# Controller_SolarCharge.net
KiCad netlist of a schematic drawn in Altium Designer
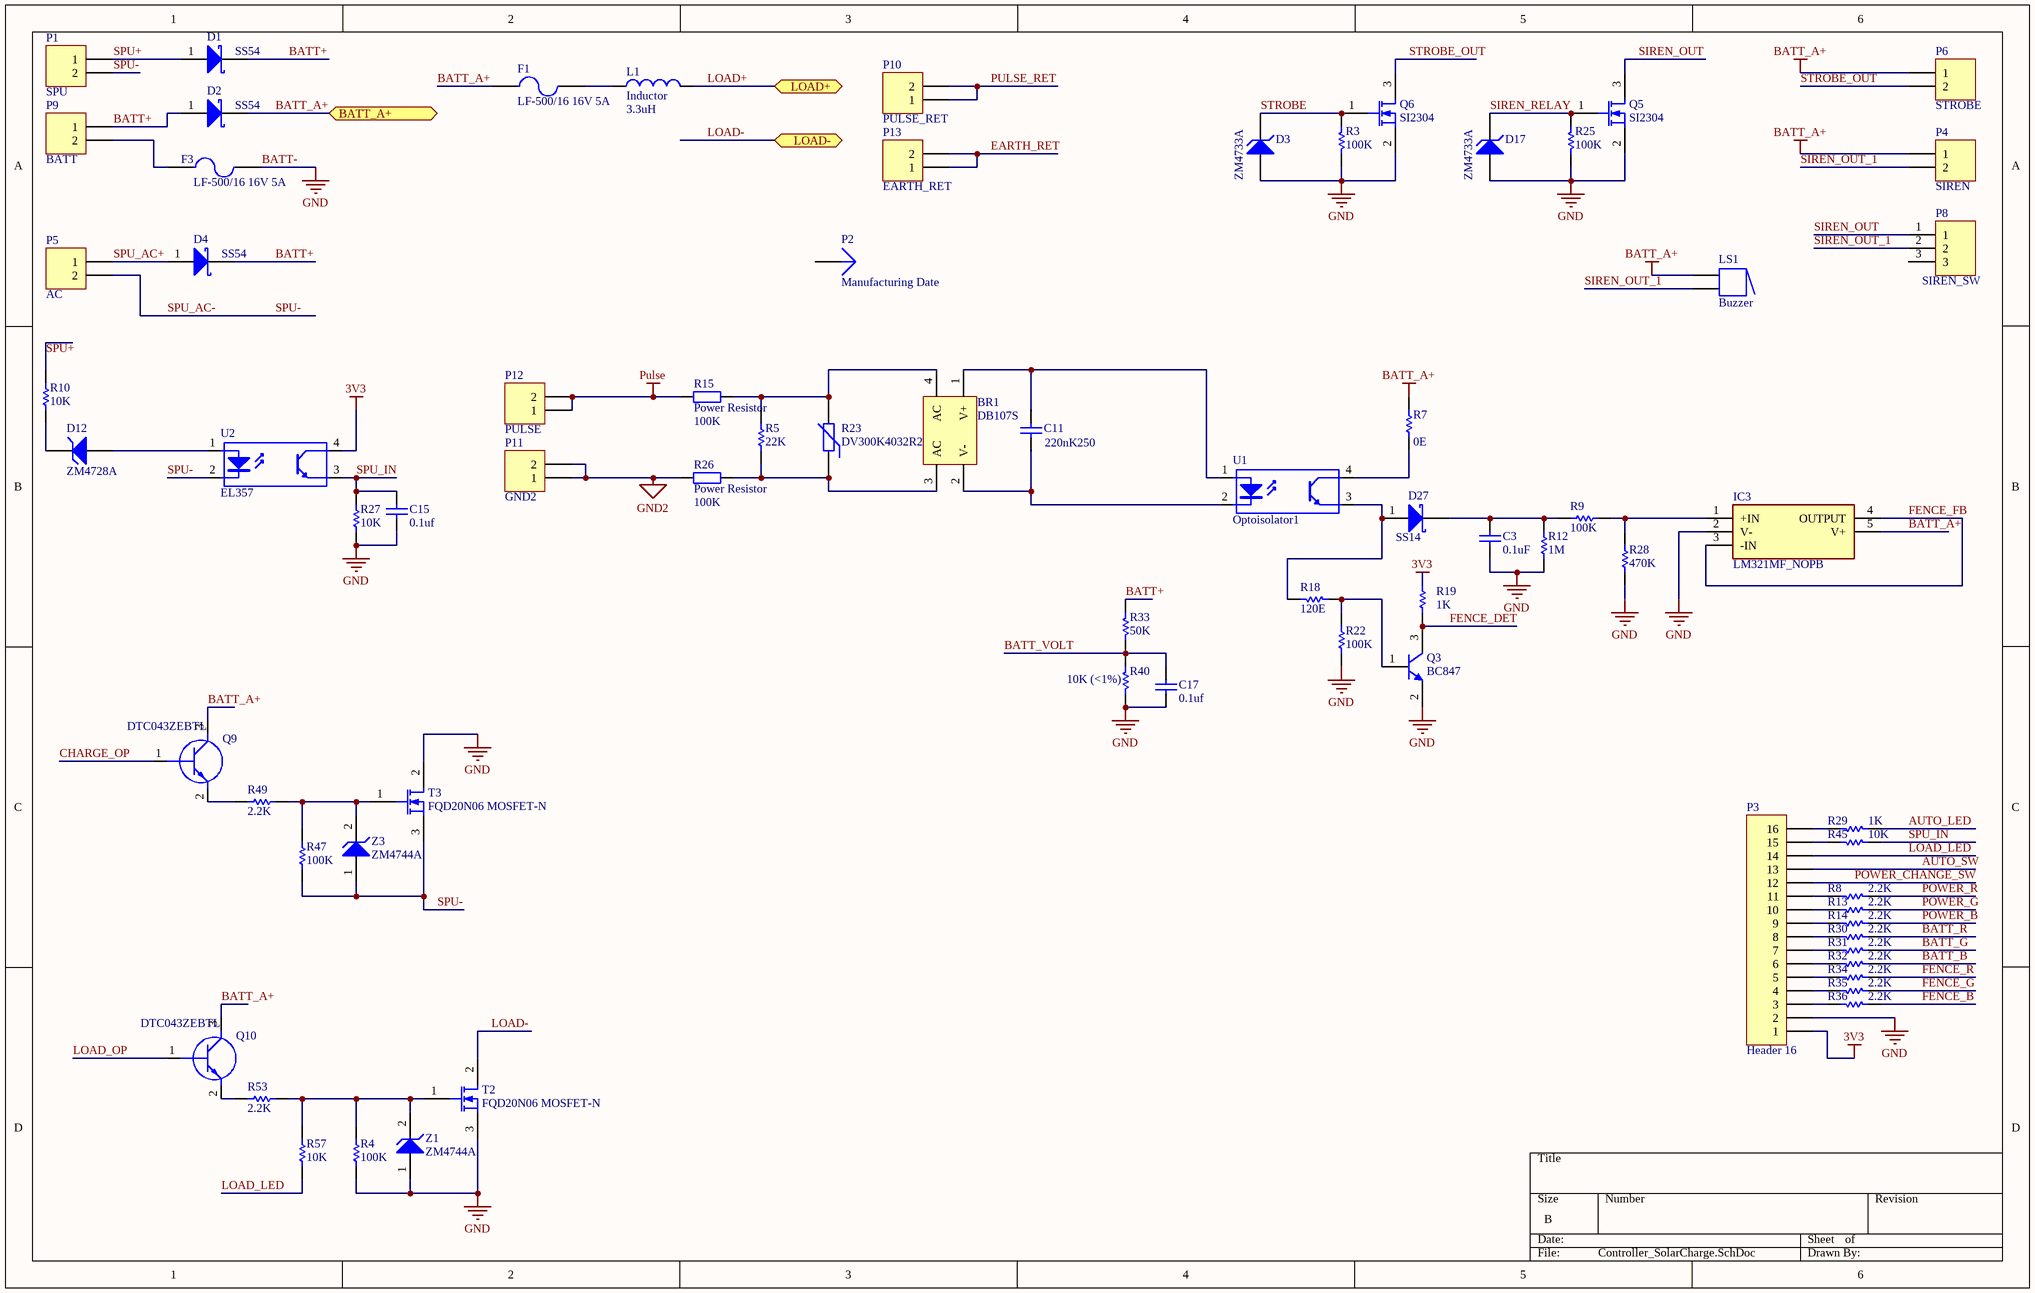
[diagram p0: Controller_SolarCharge.SchDoc]

(export (version "E")
  (design (tool "Eeschema 10.0.6"))
  (components
    (comp (ref "BR1")
      (value "DB107S")
      (footprint "DB-S_Bridge Rectifier")
      (description "Diode Bridge")
      (fields (field (name "PUBLISHER") "Altium Limited"))
      (libsource (lib "Miscellaneous Devices") (part "Bridge2"))
    )
    (comp (ref "C3")
      (value "0.1uF")
      (footprint "0805")
      (description "Capacitor")
      (fields (field (name "Comment") "Cap") (field (name "PUBLISHER") "Altium Limited"))
      (libsource (lib "Miscellaneous Devices") (part "Cap"))
    )
    (comp (ref "C11")
      (value "220nK250")
      (footprint "RES AXIAL-0.6")
      (description "Capacitor")
      (fields (field (name "Comment") "Cap") (field (name "PUBLISHER") "Altium Limited"))
      (libsource (lib "Miscellaneous Devices") (part "Cap"))
    )
    (comp (ref "C15")
      (value "0.1uf")
      (footprint "0805")
      (description "Capacitor")
      (fields (field (name "Comment") "Cap") (field (name "PUBLISHER") "Altium Limited"))
      (libsource (lib "Miscellaneous Devices") (part "Cap"))
    )
    (comp (ref "C17")
      (value "0.1uf")
      (footprint "0805")
      (description "Capacitor")
      (fields (field (name "Comment") "Cap") (field (name "PUBLISHER") "Altium Limited"))
      (libsource (lib "Miscellaneous Devices") (part "Cap"))
    )
    (comp (ref "D1")
      (value "SS54")
      (footprint "SMC")
      (description "Silicon RF Schottky Diode for Mixer Applications in the VHF/UHF Range")
      (fields (field (name "PUBLISHER") "Altium Limited"))
      (libsource (lib "Miscellaneous Devices") (part "Diode BAT17"))
    )
    (comp (ref "D2")
      (value "SS54")
      (footprint "SMDlibrary:SMC")
      (description "Silicon RF Schottky Diode for Mixer Applications in the VHF/UHF Range")
      (fields (field (name "PUBLISHER") "Altium Limited"))
      (libsource (lib "Miscellaneous Devices") (part "Diode BAT17"))
    )
    (comp (ref "D3")
      (value "ZM4733A")
      (footprint "SMA")
      (description "TVS Diode")
      (fields (field (name "PUBLISHER") "Altium Limited"))
      (libsource (lib "Miscellaneous Devices") (part "D Zener"))
    )
    (comp (ref "D4")
      (value "SS54")
      (footprint "SMDlibrary:SMC")
      (description "Silicon RF Schottky Diode for Mixer Applications in the VHF/UHF Range")
      (fields (field (name "PUBLISHER") "Altium Limited"))
      (libsource (lib "Miscellaneous Devices") (part "Diode BAT17"))
    )
    (comp (ref "D12")
      (value "ZM4728A")
      (footprint "SMDlibrary:SMA")
      (description "Zener Diode")
      (fields (field (name "PUBLISHER") "Altium Limited"))
      (libsource (lib "Miscellaneous Devices") (part "D Zener"))
    )
    (comp (ref "D17")
      (value "ZM4733A")
      (footprint "SMA")
      (description "TVS Diode")
      (fields (field (name "PUBLISHER") "Altium Limited"))
      (libsource (lib "Miscellaneous Devices") (part "D Zener"))
    )
    (comp (ref "D27")
      (value "SS14")
      (footprint "SMA")
      (description "Silicon RF Schottky Diode for Mixer Applications in the VHF/UHF Range")
      (fields (field (name "PUBLISHER") "Altium Limited"))
      (libsource (lib "Miscellaneous Devices") (part "Diode BAT17"))
    )
    (comp (ref "F1")
      (value "LF-500/16 16V 5A")
      (footprint "LF500-16")
      (description "Fuse")
      (fields (field (name "PUBLISHER") "Altium Limited"))
      (libsource (lib "Miscellaneous Devices") (part "Fuse 2"))
    )
    (comp (ref "F3")
      (value "LF-500/16 16V 5A")
      (footprint "LF500-16")
      (description "Fuse")
      (fields (field (name "PUBLISHER") "Altium Limited"))
      (libsource (lib "Miscellaneous Devices") (part "Fuse 2"))
    )
    (comp (ref "IC3")
      (value "LM321MF_NOPB")
      (footprint "SamacSys:SOT95P280X145-5N")
      (description "Integrated Circuit")
      (fields
        (field (name "MANUFACTURER_PART_NUMBER") "LM321MF/NOPB")
        (field (name "MOUSER PART NUMBER") "926-LM321MF/NOPB")
      )
      (libsource (lib "*") (part "LM321MF_NOPB"))
    )
    (comp (ref "L1")
      (value "Inductor")
      (footprint "Inductor_SMD_3.3uh")
      (fields (field (name "ALTIUM_VALUE") "3.3uH") (field (name "PUBLISHER") "Altium Limited"))
      (libsource (lib "Miscellaneous Devices") (part "Inductor"))
    )
    (comp (ref "LS1")
      (value "Buzzer")
      (footprint "BUZZER")
      (description "Magnetic Transducer Buzzer")
      (fields (field (name "PUBLISHER") "Altium Limited"))
      (libsource (lib "SchLib") (part "Buzzer"))
    )
    (comp (ref "P1")
      (value "SPU")
      (footprint "SCREW_TERMINAL 2PIN 5.08MM")
      (description "SCREW_TERMINAL 2PIN 5.08MM")
      (fields (field (name "PUBLISHER") "Altium Limited"))
      (libsource (lib "") (part "Header 2_1"))
    )
    (comp (ref "P2")
      (value "Manufacturing Date")
      (footprint "MFT_DATE")
      (description "Plug")
      (fields (field (name "PUBLISHER") "Altium Limited"))
      (libsource (lib "Miscellaneous Connectors") (part "Plug"))
    )
    (comp (ref "P3")
      (value "Header 16")
      (footprint "FPC_CON_16PIN")
      (description "Header, 16-Pin")
      (fields (field (name "PUBLISHER") "Altium Limited"))
      (libsource (lib "Miscellaneous Connectors") (part "Header 16"))
    )
    (comp (ref "P4")
      (value "SIREN")
      (footprint "SCREW_TERMINAL 2PIN 5.08MM")
      (description "SCREW_TERMINAL 2PIN 5.08MM")
      (fields (field (name "PUBLISHER") "Altium Limited"))
      (libsource (lib "Miscellaneous Connectors") (part "Header 2"))
    )
    (comp (ref "P5")
      (value "AC")
      (footprint "SCREW_TERMINAL 2PIN 5.08MM")
      (description "SCREW_TERMINAL 2PIN 5.08MM")
      (fields (field (name "PUBLISHER") "Altium Limited"))
      (libsource (lib "") (part "Header 2_1"))
    )
    (comp (ref "P6")
      (value "STROBE")
      (footprint "SCREW_TERMINAL 2PIN 5.08MM")
      (description "SCREW_TERMINAL 2PIN 5.08MM")
      (fields (field (name "PUBLISHER") "Altium Limited"))
      (libsource (lib "Miscellaneous Connectors") (part "Header 2"))
    )
    (comp (ref "P8")
      (value "SIREN_SW")
      (footprint "SWITCH_SLIDE")
      (description "Header, 3-Pin")
      (fields (field (name "PUBLISHER") "Altium Limited"))
      (libsource (lib "Miscellaneous Connectors") (part "Header 3"))
    )
    (comp (ref "P9")
      (value "BATT")
      (footprint "SCREW_TERMINAL 2PIN 5.08MM")
      (description "SCREW_TERMINAL 2PIN 5.08MM")
      (fields (field (name "PUBLISHER") "Altium Limited"))
      (libsource (lib "") (part "Header 2_1"))
    )
    (comp (ref "P10")
      (value "PULSE_RET")
      (footprint "SCREW_TERMINAL ENERGIZER")
      (description "SCREW_TERMINAL 2PIN 9.25MM")
      (fields (field (name "PUBLISHER") "Altium Limited"))
      (libsource (lib "") (part "Header 2_2"))
    )
    (comp (ref "P11")
      (value "GND2")
      (footprint "SCREW_TERMINAL ENERGIZER")
      (description "Header, 2-Pin")
      (fields (field (name "PUBLISHER") "Altium Limited"))
      (libsource (lib "") (part "Header 2_2"))
    )
    (comp (ref "P12")
      (value "PULSE")
      (footprint "SCREW_TERMINAL ENERGIZER")
      (description "SCREW_TERMINAL 2PIN 9.25MM")
      (fields (field (name "PUBLISHER") "Altium Limited"))
      (libsource (lib "") (part "Header 2_2"))
    )
    (comp (ref "P13")
      (value "EARTH_RET")
      (footprint "SCREW_TERMINAL ENERGIZER")
      (description "Header, 2-Pin")
      (fields (field (name "PUBLISHER") "Altium Limited"))
      (libsource (lib "") (part "Header 2_2"))
    )
    (comp (ref "Q3")
      (value "BC847")
      (footprint "SOT-23")
      (description "NPN General Purpose Amplifier")
      (fields (field (name "PUBLISHER") "Altium Limited"))
      (libsource (lib "Miscellaneous Devices") (part "2N3904"))
    )
    (comp (ref "Q5")
      (value "SI2304")
      (footprint "SOT-23")
      (description "SI2304 A4SHB MOSFET-N")
      (fields (field (name "PUBLISHER") "Altium Limited"))
      (libsource (lib "Miscellaneous Devices") (part "MOSFET-N"))
    )
    (comp (ref "Q6")
      (value "SI2304")
      (footprint "SOT-23")
      (description "SI2304 A4SHB MOSFET-N")
      (fields (field (name "PUBLISHER") "Altium Limited"))
      (libsource (lib "Miscellaneous Devices") (part "MOSFET-N"))
    )
    (comp (ref "Q9")
      (value "DTC043ZEBTL")
      (footprint "SOTFL50P160X85-3N")
      (description "Transistor BJT NPN")
      (fields (field (name "MOUSER PART NUMBER") "755-DTC043ZEBTL"))
      (libsource (lib "*") (part "DTC043ZEBTL"))
    )
    (comp (ref "Q10")
      (value "DTC043ZEBTL")
      (footprint "SOTFL50P160X85-3N")
      (description "Transistor BJT NPN")
      (fields (field (name "MOUSER PART NUMBER") "755-DTC043ZEBTL"))
      (libsource (lib "*") (part "DTC043ZEBTL"))
    )
    (comp (ref "R3")
      (value "100K")
      (footprint "0805")
      (description "Resistor")
      (fields (field (name "Comment") "Res1") (field (name "PUBLISHER") "Altium Limited"))
      (libsource (lib "Miscellaneous Devices") (part "Res1"))
    )
    (comp (ref "R4")
      (value "100K")
      (footprint "0805")
      (description "Resistor")
      (fields (field (name "Comment") "Res1") (field (name "PUBLISHER") "Altium Limited"))
      (libsource (lib "Miscellaneous Devices") (part "Res1"))
    )
    (comp (ref "R5")
      (value "22K")
      (footprint "POWER_RES 5W_35mm")
      (description "Resistor")
      (fields (field (name "Comment") "Res1") (field (name "PUBLISHER") "Altium Limited"))
      (libsource (lib "Miscellaneous Devices") (part "Res1"))
    )
    (comp (ref "R7")
      (value "0E")
      (footprint "0805")
      (description "Resistor")
      (fields (field (name "Comment") "Res1") (field (name "PUBLISHER") "Altium Limited"))
      (libsource (lib "Miscellaneous Devices") (part "Res1"))
    )
    (comp (ref "R8")
      (value "2.2K")
      (footprint "0805")
      (description "Resistor")
      (fields (field (name "Comment") "Res1") (field (name "PUBLISHER") "Altium Limited"))
      (libsource (lib "Miscellaneous Devices") (part "Res1"))
    )
    (comp (ref "R9")
      (value "100K")
      (footprint "0805")
      (description "Resistor")
      (fields (field (name "Comment") "Res1") (field (name "PUBLISHER") "Altium Limited"))
      (libsource (lib "Miscellaneous Devices") (part "Res1"))
    )
    (comp (ref "R10")
      (value "10K")
      (footprint "0805")
      (description "Resistor")
      (fields (field (name "Comment") "Res1") (field (name "PUBLISHER") "Altium Limited"))
      (libsource (lib "Miscellaneous Devices") (part "Res1"))
    )
    (comp (ref "R12")
      (value "1M")
      (footprint "0805")
      (description "Resistor")
      (fields (field (name "Comment") "Res1") (field (name "PUBLISHER") "Altium Limited"))
      (libsource (lib "Miscellaneous Devices") (part "Res1"))
    )
    (comp (ref "R13")
      (value "2.2K")
      (footprint "0805")
      (description "Resistor")
      (fields (field (name "Comment") "Res1") (field (name "PUBLISHER") "Altium Limited"))
      (libsource (lib "Miscellaneous Devices") (part "Res1"))
    )
    (comp (ref "R14")
      (value "2.2K")
      (footprint "SMDlibrary:0805")
      (description "Resistor")
      (fields (field (name "Comment") "Res1") (field (name "PUBLISHER") "Altium Limited"))
      (libsource (lib "Miscellaneous Devices") (part "Res1"))
    )
    (comp (ref "R15")
      (value "Power Resistor")
      (footprint "PCBLIB:POWER_RES 5W_35mm")
      (description "Resistor")
      (fields (field (name "ALTIUM_VALUE") "100K") (field (name "PUBLISHER") "Altium Limited"))
      (libsource (lib "Miscellaneous Devices") (part "Res2"))
    )
    (comp (ref "R18")
      (value "120E")
      (footprint "0805")
      (description "Resistor")
      (fields (field (name "Comment") "Res1") (field (name "PUBLISHER") "Altium Limited"))
      (libsource (lib "Miscellaneous Devices") (part "Res1"))
    )
    (comp (ref "R19")
      (value "1K")
      (footprint "0805")
      (description "Resistor")
      (fields (field (name "Comment") "Res1") (field (name "PUBLISHER") "Altium Limited"))
      (libsource (lib "Miscellaneous Devices") (part "Res1"))
    )
    (comp (ref "R22")
      (value "100K")
      (footprint "0805")
      (description "Resistor")
      (fields (field (name "Comment") "Res1") (field (name "PUBLISHER") "Altium Limited"))
      (libsource (lib "Miscellaneous Devices") (part "Res1"))
    )
    (comp (ref "R23")
      (value "DV300K4032R2")
      (footprint "3225k471")
      (description "Varistor (Voltage-Sensitive Resistor)")
      (fields (field (name "PUBLISHER") "Altium Limited"))
      (libsource (lib "Miscellaneous Devices") (part "Res Varistor"))
    )
    (comp (ref "R25")
      (value "100K")
      (footprint "0805")
      (description "Resistor")
      (fields (field (name "Comment") "Res1") (field (name "PUBLISHER") "Altium Limited"))
      (libsource (lib "Miscellaneous Devices") (part "Res1"))
    )
    (comp (ref "R26")
      (value "Power Resistor")
      (footprint "POWER_RES 5W_35mm")
      (description "Resistor")
      (fields (field (name "ALTIUM_VALUE") "100K") (field (name "PUBLISHER") "Altium Limited"))
      (libsource (lib "Miscellaneous Devices") (part "Res2"))
    )
    (comp (ref "R27")
      (value "10K")
      (footprint "0805")
      (description "Resistor")
      (fields (field (name "Comment") "Res1") (field (name "PUBLISHER") "Altium Limited"))
      (libsource (lib "Miscellaneous Devices") (part "Res1"))
    )
    (comp (ref "R28")
      (value "470K")
      (footprint "0805")
      (description "Resistor")
      (fields (field (name "Comment") "Res1") (field (name "PUBLISHER") "Altium Limited"))
      (libsource (lib "Miscellaneous Devices") (part "Res1"))
    )
    (comp (ref "R29")
      (value "1K")
      (footprint "0805")
      (description "Resistor")
      (fields (field (name "Comment") "Res1") (field (name "PUBLISHER") "Altium Limited"))
      (libsource (lib "Miscellaneous Devices") (part "Res1"))
    )
    (comp (ref "R30")
      (value "2.2K")
      (footprint "0805")
      (description "Resistor")
      (fields (field (name "Comment") "Res1") (field (name "PUBLISHER") "Altium Limited"))
      (libsource (lib "Miscellaneous Devices") (part "Res1"))
    )
    (comp (ref "R31")
      (value "2.2K")
      (footprint "0805")
      (description "Resistor")
      (fields (field (name "Comment") "Res1") (field (name "PUBLISHER") "Altium Limited"))
      (libsource (lib "Miscellaneous Devices") (part "Res1"))
    )
    (comp (ref "R32")
      (value "2.2K")
      (footprint "0805")
      (description "Resistor")
      (fields (field (name "Comment") "Res1") (field (name "PUBLISHER") "Altium Limited"))
      (libsource (lib "Miscellaneous Devices") (part "Res1"))
    )
    (comp (ref "R33")
      (value "50K")
      (footprint "0805")
      (description "Resistor")
      (fields (field (name "Comment") "Res1") (field (name "PUBLISHER") "Altium Limited"))
      (libsource (lib "Miscellaneous Devices") (part "Res1"))
    )
    (comp (ref "R34")
      (value "2.2K")
      (footprint "0805")
      (description "Resistor")
      (fields (field (name "Comment") "Res1") (field (name "PUBLISHER") "Altium Limited"))
      (libsource (lib "Miscellaneous Devices") (part "Res1"))
    )
    (comp (ref "R35")
      (value "2.2K")
      (footprint "0805")
      (description "Resistor")
      (fields (field (name "Comment") "Res1") (field (name "PUBLISHER") "Altium Limited"))
      (libsource (lib "Miscellaneous Devices") (part "Res1"))
    )
    (comp (ref "R36")
      (value "2.2K")
      (footprint "SMDlibrary:0805")
      (description "Resistor")
      (fields (field (name "Comment") "Res1") (field (name "PUBLISHER") "Altium Limited"))
      (libsource (lib "Miscellaneous Devices") (part "Res1"))
    )
    (comp (ref "R40")
      (value "10K (<1%)")
      (footprint "0805")
      (description "Resistor")
      (fields (field (name "Comment") "Res1") (field (name "PUBLISHER") "Altium Limited"))
      (libsource (lib "Miscellaneous Devices") (part "Res1"))
    )
    (comp (ref "R45")
      (value "10K")
      (footprint "0805")
      (description "Resistor")
      (fields (field (name "Comment") "Res1") (field (name "PUBLISHER") "Altium Limited"))
      (libsource (lib "Miscellaneous Devices") (part "Res1"))
    )
    (comp (ref "R47")
      (value "100K")
      (footprint "0805")
      (description "Resistor")
      (fields (field (name "Comment") "Res1") (field (name "PUBLISHER") "Altium Limited"))
      (libsource (lib "Miscellaneous Devices") (part "Res1"))
    )
    (comp (ref "R49")
      (value "2.2K")
      (footprint "0805")
      (description "Resistor")
      (fields (field (name "Comment") "Res1") (field (name "PUBLISHER") "Altium Limited"))
      (libsource (lib "Miscellaneous Devices") (part "Res1"))
    )
    (comp (ref "R53")
      (value "2.2K")
      (footprint "0805")
      (description "Resistor")
      (fields (field (name "Comment") "Res1") (field (name "PUBLISHER") "Altium Limited"))
      (libsource (lib "Miscellaneous Devices") (part "Res1"))
    )
    (comp (ref "R57")
      (value "10K")
      (footprint "0805")
      (description "Resistor")
      (fields (field (name "Comment") "Res1") (field (name "PUBLISHER") "Altium Limited"))
      (libsource (lib "Miscellaneous Devices") (part "Res1"))
    )
    (comp (ref "T2")
      (value "FQD20N06 MOSFET-N")
      (footprint "SMDlibrary:TO252 (DPAK)")
      (description "N-Channel MOSFET")
      (fields (field (name "PUBLISHER") "Altium Limited"))
      (libsource (lib "") (part "MOSFET-N_1"))
    )
    (comp (ref "T3")
      (value "FQD20N06 MOSFET-N")
      (footprint "SMDlibrary:TO252 (DPAK)")
      (description "N-Channel MOSFET")
      (fields (field (name "PUBLISHER") "Altium Limited"))
      (libsource (lib "") (part "MOSFET-N_1"))
    )
    (comp (ref "U1")
      (value "Optoisolator1")
      (footprint "IR ISOLATED")
      (description "Optocoupler for Return")
      (fields (field (name "PUBLISHER") "Altium Limited"))
      (libsource (lib "Miscellaneous Devices") (part "Optoisolator1"))
    )
    (comp (ref "U2")
      (value "EL357")
      (footprint "SOP4")
      (description "4-Pin Phototransistor Optocoupler")
      (fields (field (name "PUBLISHER") "Altium Limited"))
      (libsource (lib "Miscellaneous Devices") (part "Optoisolator1"))
    )
    (comp (ref "Z1")
      (value "ZM4744A")
      (footprint "SMDlibrary:SMA")
      (description "Zener Diode")
      (fields (field (name "PUBLISHER") "Altium Limited"))
      (libsource (lib "") (part "D Zener_1"))
    )
    (comp (ref "Z3")
      (value "ZM4744A")
      (footprint "SMDlibrary:SMA")
      (description "Zener Diode")
      (fields (field (name "PUBLISHER") "Altium Limited"))
      (libsource (lib "") (part "D Zener_1"))
    )
  )
  (nets
    (net (code "1") (name "/AUTO_LED") (class "Default")
      (node (ref "R29") (pin "1") (pinfunction "1_1") (pintype "passive"))
    )
    (net (code "2") (name "/AUTO_SW") (class "Default")
      (node (ref "P3") (pin "13") (pinfunction "13_13") (pintype "passive"))
    )
    (net (code "3") (name "/BATT+") (class "Default")
      (node (ref "D1") (pin "2") (pinfunction "2_2") (pintype "passive"))
      (node (ref "D2") (pin "1") (pinfunction "A_1") (pintype "passive"))
      (node (ref "D4") (pin "2") (pinfunction "2_2") (pintype "passive"))
      (node (ref "P9") (pin "1") (pinfunction "1_1") (pintype "passive"))
      (node (ref "R33") (pin "2") (pinfunction "2_2") (pintype "passive"))
    )
    (net (code "4") (name "/BATT_B") (class "Default")
      (node (ref "R32") (pin "1") (pinfunction "1_1") (pintype "passive"))
    )
    (net (code "5") (name "/BATT_G") (class "Default")
      (node (ref "R31") (pin "1") (pinfunction "1_1") (pintype "passive"))
    )
    (net (code "6") (name "/BATT_R") (class "Default")
      (node (ref "R30") (pin "1") (pinfunction "1_1") (pintype "passive"))
    )
    (net (code "7") (name "/BATT_VOLT") (class "Default")
      (node (ref "C17") (pin "1") (pinfunction "1_1") (pintype "passive"))
      (node (ref "R33") (pin "1") (pinfunction "1_1") (pintype "passive"))
      (node (ref "R40") (pin "2") (pinfunction "2_2") (pintype "passive"))
    )
    (net (code "8") (name "/CHARGE_OP") (class "Default")
      (node (ref "Q9") (pin "1") (pinfunction "B_1") (pintype "passive"))
    )
    (net (code "9") (name "/EARTH_RET") (class "Default")
      (node (ref "P13") (pin "1") (pinfunction "1_1") (pintype "passive"))
      (node (ref "P13") (pin "2") (pinfunction "2_2") (pintype "passive"))
    )
    (net (code "10") (name "/FENCE_B") (class "Default")
      (node (ref "R36") (pin "1") (pinfunction "1_1") (pintype "passive"))
    )
    (net (code "11") (name "/FENCE_DET") (class "Default")
      (node (ref "Q3") (pin "3") (pinfunction "C_3") (pintype "passive"))
      (node (ref "R19") (pin "1") (pinfunction "1_1") (pintype "passive"))
    )
    (net (code "12") (name "/FENCE_FB") (class "Default")
      (node (ref "IC3") (pin "3") (pinfunction "-IN_3") (pintype "passive"))
      (node (ref "IC3") (pin "4") (pinfunction "OUTPUT_4") (pintype "passive"))
    )
    (net (code "13") (name "/FENCE_G") (class "Default")
      (node (ref "R35") (pin "1") (pinfunction "1_1") (pintype "passive"))
    )
    (net (code "14") (name "/FENCE_R") (class "Default")
      (node (ref "R34") (pin "1") (pinfunction "1_1") (pintype "passive"))
    )
    (net (code "15") (name "/LOAD+") (class "Default")
      (node (ref "L1") (pin "2") (pinfunction "2_2") (pintype "passive"))
    )
    (net (code "16") (name "/LOAD-") (class "Default")
      (node (ref "T2") (pin "2") (pinfunction "D_2") (pintype "passive"))
    )
    (net (code "17") (name "/LOAD_LED") (class "Default")
      (node (ref "P3") (pin "14") (pinfunction "14_14") (pintype "passive"))
      (node (ref "R57") (pin "1") (pinfunction "1_1") (pintype "passive"))
    )
    (net (code "18") (name "/LOAD_OP") (class "Default")
      (node (ref "Q10") (pin "1") (pinfunction "B_1") (pintype "passive"))
    )
    (net (code "19") (name "/POWER_B") (class "Default")
      (node (ref "R14") (pin "1") (pinfunction "1_1") (pintype "passive"))
    )
    (net (code "20") (name "/POWER_CHANGE_SW") (class "Default")
      (node (ref "P3") (pin "12") (pinfunction "12_12") (pintype "passive"))
    )
    (net (code "21") (name "/POWER_G") (class "Default")
      (node (ref "R13") (pin "1") (pinfunction "1_1") (pintype "passive"))
    )
    (net (code "22") (name "/POWER_R") (class "Default")
      (node (ref "R8") (pin "1") (pinfunction "1_1") (pintype "passive"))
    )
    (net (code "23") (name "/PULSE_RET") (class "Default")
      (node (ref "P10") (pin "1") (pinfunction "1_1") (pintype "passive"))
      (node (ref "P10") (pin "2") (pinfunction "2_2") (pintype "passive"))
    )
    (net (code "24") (name "/SIREN_OUT") (class "Default")
      (node (ref "P8") (pin "1") (pinfunction "1_1") (pintype "passive"))
      (node (ref "Q5") (pin "3") (pinfunction "D_3") (pintype "passive"))
    )
    (net (code "25") (name "/SIREN_OUT_1") (class "Default")
      (node (ref "LS1") (pin "2") (pinfunction "2_2") (pintype "passive"))
      (node (ref "P4") (pin "2") (pinfunction "2_2") (pintype "passive"))
      (node (ref "P8") (pin "2") (pinfunction "2_2") (pintype "passive"))
    )
    (net (code "26") (name "/SIREN_RELAY") (class "Default")
      (node (ref "D17") (pin "2") (pinfunction "K_2") (pintype "passive"))
      (node (ref "Q5") (pin "1") (pinfunction "G_1") (pintype "passive"))
      (node (ref "R25") (pin "2") (pinfunction "2_2") (pintype "passive"))
    )
    (net (code "27") (name "/SPU+") (class "Default")
      (node (ref "D1") (pin "1") (pinfunction "A_1") (pintype "passive"))
      (node (ref "P1") (pin "1") (pinfunction "1_1") (pintype "passive"))
      (node (ref "R10") (pin "2") (pinfunction "2_2") (pintype "passive"))
    )
    (net (code "28") (name "/SPU-") (class "Default")
      (node (ref "P1") (pin "2") (pinfunction "2_2") (pintype "passive"))
      (node (ref "P5") (pin "2") (pinfunction "2_2") (pintype "passive"))
      (node (ref "R47") (pin "1") (pinfunction "1_1") (pintype "passive"))
      (node (ref "T3") (pin "3") (pinfunction "S_3") (pintype "passive"))
      (node (ref "U2") (pin "2") (pinfunction "K_2") (pintype "passive"))
      (node (ref "Z3") (pin "1") (pinfunction "A_1") (pintype "passive"))
    )
    (net (code "29") (name "/SPU_AC+") (class "Default")
      (node (ref "D4") (pin "1") (pinfunction "A_1") (pintype "passive"))
      (node (ref "P5") (pin "1") (pinfunction "1_1") (pintype "passive"))
    )
    (net (code "30") (name "/SPU_IN") (class "Default")
      (node (ref "C15") (pin "2") (pinfunction "2_2") (pintype "passive"))
      (node (ref "R27") (pin "2") (pinfunction "2_2") (pintype "passive"))
      (node (ref "R45") (pin "1") (pinfunction "1_1") (pintype "passive"))
      (node (ref "U2") (pin "3") (pinfunction "E_3") (pintype "passive"))
    )
    (net (code "31") (name "/STROBE") (class "Default")
      (node (ref "D3") (pin "2") (pinfunction "K_2") (pintype "passive"))
      (node (ref "Q6") (pin "1") (pinfunction "G_1") (pintype "passive"))
      (node (ref "R3") (pin "2") (pinfunction "2_2") (pintype "passive"))
    )
    (net (code "32") (name "/STROBE_OUT") (class "Default")
      (node (ref "P6") (pin "2") (pinfunction "2_2") (pintype "passive"))
      (node (ref "Q6") (pin "3") (pinfunction "D_3") (pintype "passive"))
    )
    (net (code "33") (name "3V3") (class "Default")
      (node (ref "P3") (pin "1") (pinfunction "1_1") (pintype "passive"))
      (node (ref "R19") (pin "2") (pinfunction "2_2") (pintype "passive"))
      (node (ref "U2") (pin "4") (pinfunction "C_4") (pintype "passive"))
    )
    (net (code "34") (name "BATT_A+") (class "Default")
      (node (ref "D2") (pin "2") (pinfunction "2_2") (pintype "passive"))
      (node (ref "F1") (pin "1") (pinfunction "1_1") (pintype "passive"))
      (node (ref "IC3") (pin "5") (pinfunction "V+_5") (pintype "passive"))
      (node (ref "LS1") (pin "1") (pinfunction "1_1") (pintype "passive"))
      (node (ref "P4") (pin "1") (pinfunction "1_1") (pintype "passive"))
      (node (ref "P6") (pin "1") (pinfunction "1_1") (pintype "passive"))
      (node (ref "Q10") (pin "3") (pinfunction "C_3") (pintype "passive"))
      (node (ref "Q9") (pin "3") (pinfunction "C_3") (pintype "passive"))
      (node (ref "R7") (pin "2") (pinfunction "2_2") (pintype "passive"))
    )
    (net (code "35") (name "GND") (class "Default")
      (node (ref "C15") (pin "1") (pinfunction "1_1") (pintype "passive"))
      (node (ref "C17") (pin "2") (pinfunction "2_2") (pintype "passive"))
      (node (ref "C3") (pin "2") (pinfunction "2_2") (pintype "passive"))
      (node (ref "D17") (pin "1") (pinfunction "A_1") (pintype "passive"))
      (node (ref "D3") (pin "1") (pinfunction "A_1") (pintype "passive"))
      (node (ref "F3") (pin "2") (pinfunction "2_2") (pintype "passive"))
      (node (ref "IC3") (pin "2") (pinfunction "V-_2") (pintype "passive"))
      (node (ref "P3") (pin "2") (pinfunction "2_2") (pintype "passive"))
      (node (ref "Q3") (pin "2") (pinfunction "E_2") (pintype "passive"))
      (node (ref "Q5") (pin "2") (pinfunction "S_2") (pintype "passive"))
      (node (ref "Q6") (pin "2") (pinfunction "S_2") (pintype "passive"))
      (node (ref "R12") (pin "1") (pinfunction "1_1") (pintype "passive"))
      (node (ref "R22") (pin "1") (pinfunction "1_1") (pintype "passive"))
      (node (ref "R25") (pin "1") (pinfunction "1_1") (pintype "passive"))
      (node (ref "R27") (pin "1") (pinfunction "1_1") (pintype "passive"))
      (node (ref "R28") (pin "1") (pinfunction "1_1") (pintype "passive"))
      (node (ref "R3") (pin "1") (pinfunction "1_1") (pintype "passive"))
      (node (ref "R4") (pin "1") (pinfunction "1_1") (pintype "passive"))
      (node (ref "R40") (pin "1") (pinfunction "1_1") (pintype "passive"))
      (node (ref "T2") (pin "3") (pinfunction "S_3") (pintype "passive"))
      (node (ref "T3") (pin "2") (pinfunction "D_2") (pintype "passive"))
      (node (ref "Z1") (pin "1") (pinfunction "A_1") (pintype "passive"))
    )
    (net (code "36") (name "GND2") (class "Default")
      (node (ref "P11") (pin "1") (pinfunction "1_1") (pintype "passive"))
      (node (ref "P11") (pin "2") (pinfunction "2_2") (pintype "passive"))
      (node (ref "R26") (pin "1") (pinfunction "1_1") (pintype "passive"))
    )
    (net (code "37") (name "Net-(BR1-AC-Pad3)") (class "Default")
      (node (ref "BR1") (pin "3") (pinfunction "AC_3") (pintype "passive"))
      (node (ref "R23") (pin "1") (pinfunction "1_1") (pintype "passive"))
      (node (ref "R26") (pin "2") (pinfunction "2_2") (pintype "passive"))
      (node (ref "R5") (pin "2") (pinfunction "2_2") (pintype "passive"))
    )
    (net (code "38") (name "Net-(BR1-AC-Pad4)") (class "Default")
      (node (ref "BR1") (pin "4") (pinfunction "AC_4") (pintype "passive"))
      (node (ref "R15") (pin "2") (pinfunction "2_2") (pintype "passive"))
      (node (ref "R23") (pin "2") (pinfunction "2_2") (pintype "passive"))
      (node (ref "R5") (pin "1") (pinfunction "1_1") (pintype "passive"))
    )
    (net (code "39") (name "Net-(BR1-V+)") (class "Default")
      (node (ref "BR1") (pin "1") (pinfunction "V+_1") (pintype "passive"))
      (node (ref "C11") (pin "2") (pinfunction "2_2") (pintype "passive"))
      (node (ref "U1") (pin "1") (pinfunction "A_1") (pintype "passive"))
    )
    (net (code "40") (name "Net-(BR1-V-)") (class "Default")
      (node (ref "BR1") (pin "2") (pinfunction "V-_2") (pintype "passive"))
      (node (ref "C11") (pin "1") (pinfunction "1_1") (pintype "passive"))
      (node (ref "U1") (pin "2") (pinfunction "K_2") (pintype "passive"))
    )
    (net (code "41") (name "Net-(C3-Pad1)") (class "Default")
      (node (ref "C3") (pin "1") (pinfunction "1_1") (pintype "passive"))
      (node (ref "D27") (pin "2") (pinfunction "2_2") (pintype "passive"))
      (node (ref "R12") (pin "2") (pinfunction "2_2") (pintype "passive"))
      (node (ref "R9") (pin "2") (pinfunction "2_2") (pintype "passive"))
    )
    (net (code "42") (name "Net-(D12-A)") (class "Default")
      (node (ref "D12") (pin "1") (pinfunction "A_1") (pintype "passive"))
      (node (ref "U2") (pin "1") (pinfunction "A_1") (pintype "passive"))
    )
    (net (code "43") (name "Net-(D12-K)") (class "Default")
      (node (ref "D12") (pin "2") (pinfunction "K_2") (pintype "passive"))
      (node (ref "R10") (pin "1") (pinfunction "1_1") (pintype "passive"))
    )
    (net (code "44") (name "Net-(D27-A)") (class "Default")
      (node (ref "D27") (pin "1") (pinfunction "A_1") (pintype "passive"))
      (node (ref "R18") (pin "2") (pinfunction "2_2") (pintype "passive"))
      (node (ref "U1") (pin "3") (pinfunction "E_3") (pintype "passive"))
    )
    (net (code "45") (name "Net-(F1-Pad2)") (class "Default")
      (node (ref "F1") (pin "2") (pinfunction "2_2") (pintype "passive"))
      (node (ref "L1") (pin "1") (pinfunction "1_1") (pintype "passive"))
    )
    (net (code "46") (name "Net-(F3-Pad1)") (class "Default")
      (node (ref "F3") (pin "1") (pinfunction "1_1") (pintype "passive"))
      (node (ref "P9") (pin "2") (pinfunction "2_2") (pintype "passive"))
    )
    (net (code "47") (name "Net-(IC3-+IN)") (class "Default")
      (node (ref "IC3") (pin "1") (pinfunction "+IN_1") (pintype "passive"))
      (node (ref "R28") (pin "2") (pinfunction "2_2") (pintype "passive"))
      (node (ref "R9") (pin "1") (pinfunction "1_1") (pintype "passive"))
    )
    (net (code "48") (name "Net-(P3-Pad3)") (class "Default")
      (node (ref "P3") (pin "3") (pinfunction "3_3") (pintype "passive"))
      (node (ref "R36") (pin "2") (pinfunction "2_2") (pintype "passive"))
    )
    (net (code "49") (name "Net-(P3-Pad4)") (class "Default")
      (node (ref "P3") (pin "4") (pinfunction "4_4") (pintype "passive"))
      (node (ref "R35") (pin "2") (pinfunction "2_2") (pintype "passive"))
    )
    (net (code "50") (name "Net-(P3-Pad5)") (class "Default")
      (node (ref "P3") (pin "5") (pinfunction "5_5") (pintype "passive"))
      (node (ref "R34") (pin "2") (pinfunction "2_2") (pintype "passive"))
    )
    (net (code "51") (name "Net-(P3-Pad6)") (class "Default")
      (node (ref "P3") (pin "6") (pinfunction "6_6") (pintype "passive"))
      (node (ref "R32") (pin "2") (pinfunction "2_2") (pintype "passive"))
    )
    (net (code "52") (name "Net-(P3-Pad7)") (class "Default")
      (node (ref "P3") (pin "7") (pinfunction "7_7") (pintype "passive"))
      (node (ref "R31") (pin "2") (pinfunction "2_2") (pintype "passive"))
    )
    (net (code "53") (name "Net-(P3-Pad8)") (class "Default")
      (node (ref "P3") (pin "8") (pinfunction "8_8") (pintype "passive"))
      (node (ref "R30") (pin "2") (pinfunction "2_2") (pintype "passive"))
    )
    (net (code "54") (name "Net-(P3-Pad9)") (class "Default")
      (node (ref "P3") (pin "9") (pinfunction "9_9") (pintype "passive"))
      (node (ref "R14") (pin "2") (pinfunction "2_2") (pintype "passive"))
    )
    (net (code "55") (name "Net-(P3-Pad10)") (class "Default")
      (node (ref "P3") (pin "10") (pinfunction "10_10") (pintype "passive"))
      (node (ref "R13") (pin "2") (pinfunction "2_2") (pintype "passive"))
    )
    (net (code "56") (name "Net-(P3-Pad11)") (class "Default")
      (node (ref "P3") (pin "11") (pinfunction "11_11") (pintype "passive"))
      (node (ref "R8") (pin "2") (pinfunction "2_2") (pintype "passive"))
    )
    (net (code "57") (name "Net-(P3-Pad15)") (class "Default")
      (node (ref "P3") (pin "15") (pinfunction "15_15") (pintype "passive"))
      (node (ref "R45") (pin "2") (pinfunction "2_2") (pintype "passive"))
    )
    (net (code "58") (name "Net-(P3-Pad16)") (class "Default")
      (node (ref "P3") (pin "16") (pinfunction "16_16") (pintype "passive"))
      (node (ref "R29") (pin "2") (pinfunction "2_2") (pintype "passive"))
    )
    (net (code "59") (name "Net-(Q3-B)") (class "Default")
      (node (ref "Q3") (pin "1") (pinfunction "B_1") (pintype "passive"))
      (node (ref "R18") (pin "1") (pinfunction "1_1") (pintype "passive"))
      (node (ref "R22") (pin "2") (pinfunction "2_2") (pintype "passive"))
    )
    (net (code "60") (name "Net-(Q9-E)") (class "Default")
      (node (ref "Q9") (pin "2") (pinfunction "E_2") (pintype "passive"))
      (node (ref "R49") (pin "2") (pinfunction "2_2") (pintype "passive"))
    )
    (net (code "61") (name "Net-(Q10-E)") (class "Default")
      (node (ref "Q10") (pin "2") (pinfunction "E_2") (pintype "passive"))
      (node (ref "R53") (pin "2") (pinfunction "2_2") (pintype "passive"))
    )
    (net (code "62") (name "Net-(T2-G)") (class "Default")
      (node (ref "R4") (pin "2") (pinfunction "2_2") (pintype "passive"))
      (node (ref "R53") (pin "1") (pinfunction "1_1") (pintype "passive"))
      (node (ref "R57") (pin "2") (pinfunction "2_2") (pintype "passive"))
      (node (ref "T2") (pin "1") (pinfunction "G_1") (pintype "passive"))
      (node (ref "Z1") (pin "2") (pinfunction "K_2") (pintype "passive"))
    )
    (net (code "63") (name "Net-(T3-G)") (class "Default")
      (node (ref "R47") (pin "2") (pinfunction "2_2") (pintype "passive"))
      (node (ref "R49") (pin "1") (pinfunction "1_1") (pintype "passive"))
      (node (ref "T3") (pin "1") (pinfunction "G_1") (pintype "passive"))
      (node (ref "Z3") (pin "2") (pinfunction "K_2") (pintype "passive"))
    )
    (net (code "64") (name "Net-(U1-C)") (class "Default")
      (node (ref "R7") (pin "1") (pinfunction "1_1") (pintype "passive"))
      (node (ref "U1") (pin "4") (pinfunction "C_4") (pintype "passive"))
    )
    (net (code "65") (name "Pulse") (class "Default")
      (node (ref "P12") (pin "1") (pinfunction "1_1") (pintype "passive"))
      (node (ref "P12") (pin "2") (pinfunction "2_2") (pintype "passive"))
      (node (ref "R15") (pin "1") (pinfunction "1_1") (pintype "passive"))
    )
    (net (code "66") (name "unconnected-(P2-Pad1)") (class "Default")
      (node (ref "P2") (pin "1") (pinfunction "1_1") (pintype "passive"))
    )
    (net (code "67") (name "unconnected-(P8-Pad3)") (class "Default")
      (node (ref "P8") (pin "3") (pinfunction "3_3") (pintype "passive"))
    )
  )
)
